# REV5.net
KiCad netlist of a schematic drawn in EasyEDA Pro
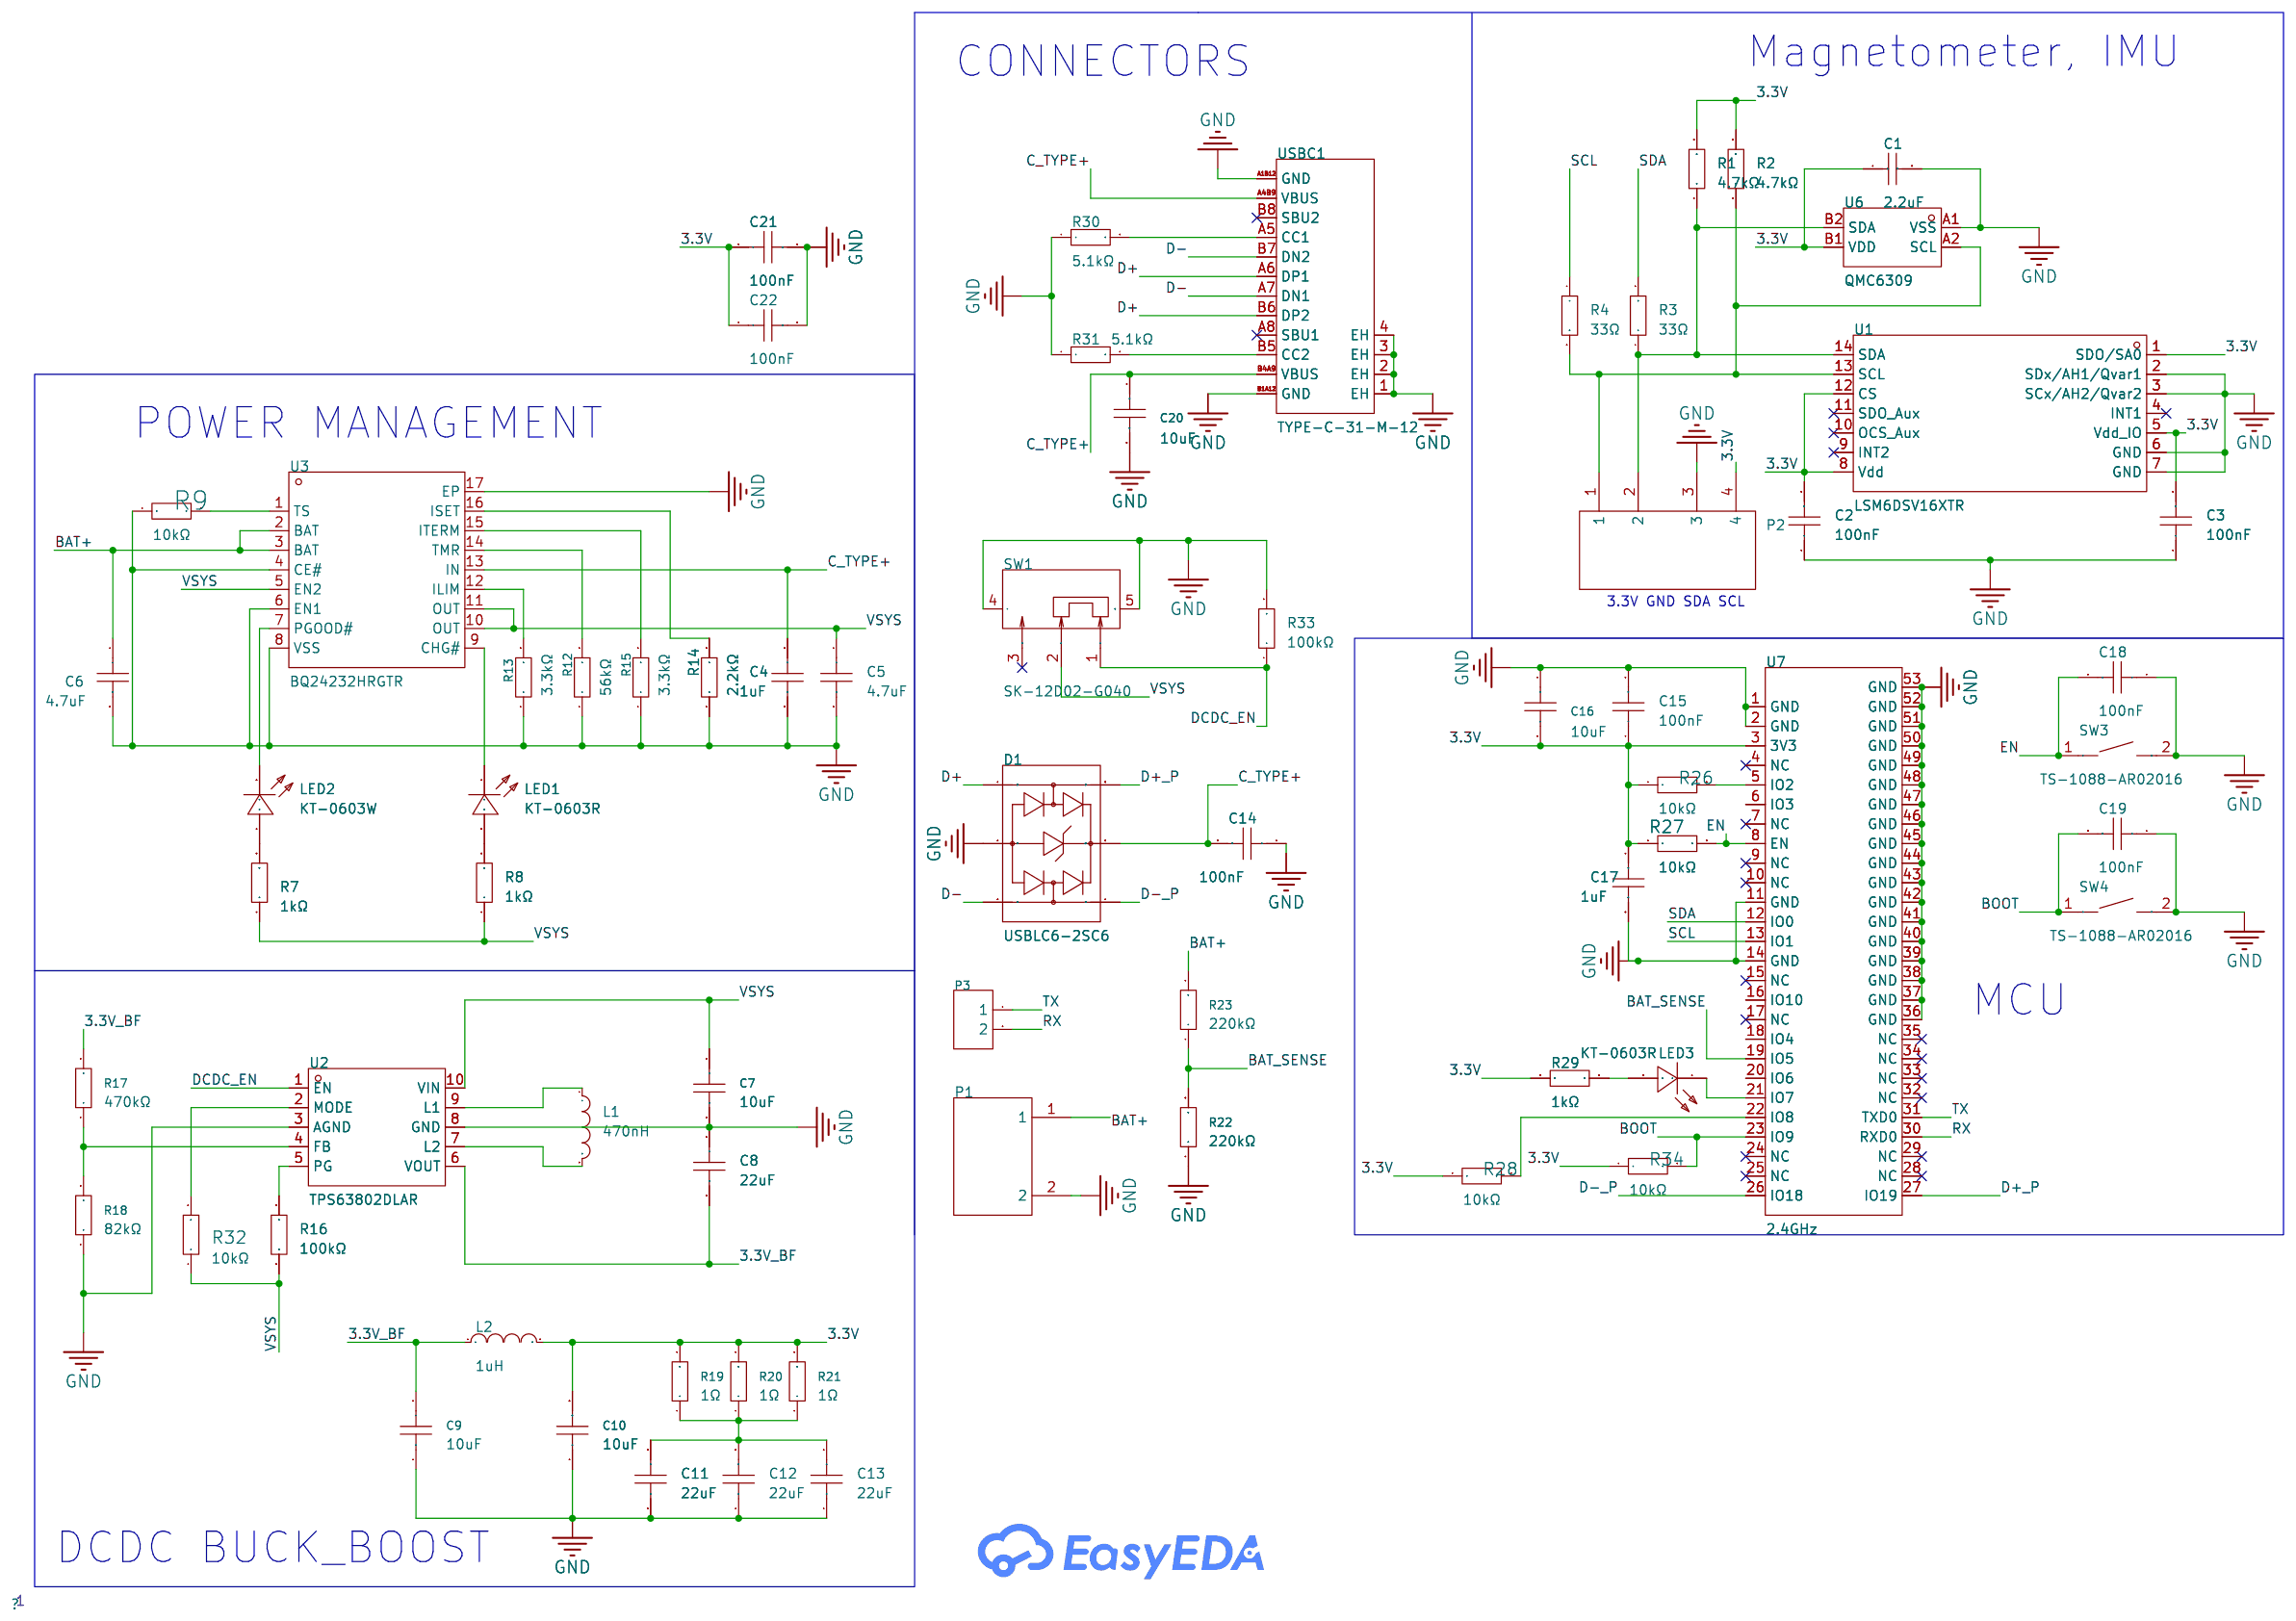
[diagram p0: schematic sheet]

(export (version "E")
  (design (tool "Eeschema 10.0.6"))
  (components
    (comp (ref "C1")
      (value "2.2uF")
      (footprint "easyedapro:C0603")
      (description "Capacitance:2.2uF Tolerance:±10% Tolerance:±10% Voltage Rating:16V Temperature Coefficient:X5R")
      (fields
        (field (name "Manufacturer Part") "CL10A225KO8NNNC")
        (field (name "Manufacturer") "SAMSUNG(三星)")
      )
      (libsource (lib "easyedapro") (part "CL10A225KO8NNNC"))
    )
    (comp (ref "C2")
      (value "100nF")
      (footprint "easyedapro:C0603")
      (description "Capacitance:100nF Tolerance:±10% Tolerance:±10% Voltage Rating:50V Temperature Coefficient:X7R")
      (fields
        (field (name "Manufacturer Part") "CC0603KRX7R9BB104")
        (field (name "Manufacturer") "YAGEO(国巨)")
      )
      (libsource (lib "easyedapro") (part "CC0603KRX7R9BB104"))
    )
    (comp (ref "C3")
      (value "100nF")
      (footprint "easyedapro:C0603")
      (description "Capacitance:100nF Tolerance:±10% Tolerance:±10% Voltage Rating:50V Temperature Coefficient:X7R")
      (fields
        (field (name "Manufacturer Part") "CC0603KRX7R9BB104")
        (field (name "Manufacturer") "YAGEO(国巨)")
      )
      (libsource (lib "easyedapro") (part "CC0603KRX7R9BB104"))
    )
    (comp (ref "C4")
      (value "1uF")
      (footprint "easyedapro:C0603")
      (description "Capacitance:1uF Tolerance:±10% Tolerance:±10% Voltage Rating:50V Temperature Coefficient:X5R")
      (fields
        (field (name "Manufacturer Part") "CL10A105KB8NNNC")
        (field (name "Manufacturer") "SAMSUNG(三星)")
      )
      (libsource (lib "easyedapro") (part "CL10A105KB8NNNC"))
    )
    (comp (ref "C5")
      (value "4.7uF")
      (footprint "easyedapro:C0603")
      (description "Capacitance:4.7uF Tolerance:±10% Tolerance:±10% Voltage Rating:16V Temperature Coefficient:X5R")
      (fields
        (field (name "Manufacturer Part") "CL10A475KO8NNNC")
        (field (name "Manufacturer") "SAMSUNG(三星)")
      )
      (libsource (lib "easyedapro") (part "CL10A475KO8NNNC"))
    )
    (comp (ref "C6")
      (value "4.7uF")
      (footprint "easyedapro:C0603")
      (description "Capacitance:4.7uF Tolerance:±10% Tolerance:±10% Voltage Rating:16V Temperature Coefficient:X5R")
      (fields
        (field (name "Manufacturer Part") "CL10A475KO8NNNC")
        (field (name "Manufacturer") "SAMSUNG(三星)")
      )
      (libsource (lib "easyedapro") (part "CL10A475KO8NNNC"))
    )
    (comp (ref "C7")
      (value "10uF")
      (footprint "easyedapro:C0603")
      (description "Capacitance:10uF Tolerance:±20% Tolerance:±20% Voltage Rating:25V Temperature Coefficient:X5R")
      (fields
        (field (name "Manufacturer Part") "CL10A106MA8NRNC")
        (field (name "Manufacturer") "SAMSUNG(三星)")
      )
      (libsource (lib "easyedapro") (part "CL10A106MA8NRNC"))
    )
    (comp (ref "C8")
      (value "22uF")
      (footprint "easyedapro:C0805")
      (description "Capacitance:22uF Tolerance:±20% Tolerance:±20% Voltage Rating:25V Temperature Coefficient:X5R")
      (fields
        (field (name "Manufacturer Part") "CL21A226MAQNNNE")
        (field (name "Manufacturer") "SAMSUNG(三星)")
      )
      (libsource (lib "easyedapro") (part "CL21A226MAQNNNE"))
    )
    (comp (ref "C9")
      (value "10uF")
      (footprint "easyedapro:C0603")
      (description "Capacitance:10uF Tolerance:±20% Tolerance:±20% Voltage Rating:25V Temperature Coefficient:X5R")
      (fields
        (field (name "Manufacturer Part") "CL10A106MA8NRNC")
        (field (name "Manufacturer") "SAMSUNG(三星)")
      )
      (libsource (lib "easyedapro") (part "CL10A106MA8NRNC"))
    )
    (comp (ref "C10")
      (value "10uF")
      (footprint "easyedapro:C0603")
      (description "Capacitance:10uF Tolerance:±20% Tolerance:±20% Voltage Rating:25V Temperature Coefficient:X5R")
      (fields
        (field (name "Manufacturer Part") "CL10A106MA8NRNC")
        (field (name "Manufacturer") "SAMSUNG(三星)")
      )
      (libsource (lib "easyedapro") (part "CL10A106MA8NRNC"))
    )
    (comp (ref "C11")
      (value "22uF")
      (footprint "easyedapro:C0805")
      (description "Capacitance:22uF Tolerance:±20% Tolerance:±20% Voltage Rating:25V Temperature Coefficient:X5R")
      (fields
        (field (name "Manufacturer Part") "CL21A226MAQNNNE")
        (field (name "Manufacturer") "SAMSUNG(三星)")
      )
      (libsource (lib "easyedapro") (part "CL21A226MAQNNNE"))
    )
    (comp (ref "C12")
      (value "22uF")
      (footprint "easyedapro:C0805")
      (description "Capacitance:22uF Tolerance:±20% Tolerance:±20% Voltage Rating:25V Temperature Coefficient:X5R")
      (fields
        (field (name "Manufacturer Part") "CL21A226MAQNNNE")
        (field (name "Manufacturer") "SAMSUNG(三星)")
      )
      (libsource (lib "easyedapro") (part "CL21A226MAQNNNE"))
    )
    (comp (ref "C13")
      (value "22uF")
      (footprint "easyedapro:C0805")
      (description "Capacitance:22uF Tolerance:±20% Tolerance:±20% Voltage Rating:25V Temperature Coefficient:X5R")
      (fields
        (field (name "Manufacturer Part") "CL21A226MAQNNNE")
        (field (name "Manufacturer") "SAMSUNG(三星)")
      )
      (libsource (lib "easyedapro") (part "CL21A226MAQNNNE"))
    )
    (comp (ref "C14")
      (value "100nF")
      (footprint "easyedapro:C0603")
      (description "Capacitance:100nF Tolerance:±10% Tolerance:±10% Voltage Rating:50V Temperature Coefficient:X7R")
      (fields
        (field (name "Manufacturer Part") "CC0603KRX7R9BB104")
        (field (name "Manufacturer") "YAGEO(国巨)")
      )
      (libsource (lib "easyedapro") (part "CC0603KRX7R9BB104"))
    )
    (comp (ref "C15")
      (value "100nF")
      (footprint "easyedapro:C0603")
      (description "Capacitance:100nF Tolerance:±10% Tolerance:±10% Voltage Rating:50V Temperature Coefficient:X7R")
      (fields
        (field (name "Manufacturer Part") "CC0603KRX7R9BB104")
        (field (name "Manufacturer") "YAGEO(国巨)")
      )
      (libsource (lib "easyedapro") (part "CC0603KRX7R9BB104"))
    )
    (comp (ref "C16")
      (value "10uF")
      (footprint "easyedapro:C0603")
      (description "Capacitance:10uF Tolerance:±20% Tolerance:±20% Voltage Rating:25V Temperature Coefficient:X5R")
      (fields
        (field (name "Manufacturer Part") "CL10A106MA8NRNC")
        (field (name "Manufacturer") "SAMSUNG(三星)")
      )
      (libsource (lib "easyedapro") (part "CL10A106MA8NRNC"))
    )
    (comp (ref "C17")
      (value "1uF")
      (footprint "easyedapro:C0603")
      (description "Capacitance:1uF Tolerance:±10% Tolerance:±10% Voltage Rating:50V Temperature Coefficient:X5R")
      (fields
        (field (name "Manufacturer Part") "CL10A105KB8NNNC")
        (field (name "Manufacturer") "SAMSUNG(三星)")
      )
      (libsource (lib "easyedapro") (part "CL10A105KB8NNNC"))
    )
    (comp (ref "C18")
      (value "100nF")
      (footprint "easyedapro:C0603")
      (description "Capacitance:100nF Tolerance:±10% Tolerance:±10% Voltage Rating:50V Temperature Coefficient:X7R")
      (fields
        (field (name "Manufacturer Part") "CC0603KRX7R9BB104")
        (field (name "Manufacturer") "YAGEO(国巨)")
      )
      (libsource (lib "easyedapro") (part "CC0603KRX7R9BB104"))
    )
    (comp (ref "C19")
      (value "100nF")
      (footprint "easyedapro:C0603")
      (description "Capacitance:100nF Tolerance:±10% Tolerance:±10% Voltage Rating:50V Temperature Coefficient:X7R")
      (fields
        (field (name "Manufacturer Part") "CC0603KRX7R9BB104")
        (field (name "Manufacturer") "YAGEO(国巨)")
      )
      (libsource (lib "easyedapro") (part "CC0603KRX7R9BB104"))
    )
    (comp (ref "C20")
      (value "10uF")
      (footprint "easyedapro:C0603")
      (description "Capacitance:10uF Tolerance:±20% Tolerance:±20% Voltage Rating:25V Temperature Coefficient:X5R")
      (fields
        (field (name "Manufacturer Part") "CL10A106MA8NRNC")
        (field (name "Manufacturer") "SAMSUNG(三星)")
      )
      (libsource (lib "easyedapro") (part "CL10A106MA8NRNC"))
    )
    (comp (ref "C21")
      (value "100nF")
      (description "Capacitance:100nF Tolerance:±10% Tolerance:±10% Voltage Rating:16V Temperature Coefficient:X7R")
      (fields
        (field (name "Manufacturer Part") "CL05B104KO5NNNC")
        (field (name "Manufacturer") "SAMSUNG(三星)")
      )
      (libsource (lib "easyedapro") (part "CL05B104KO5NNNC"))
    )
    (comp (ref "C22")
      (value "100nF")
      (description "Capacitance:100nF Tolerance:±10% Tolerance:±10% Voltage Rating:16V Temperature Coefficient:X7R")
      (fields
        (field (name "Manufacturer Part") "CL05B104KO5NNNC")
        (field (name "Manufacturer") "SAMSUNG(三星)")
      )
      (libsource (lib "easyedapro") (part "CL05B104KO5NNNC"))
    )
    (comp (ref "D1")
      (value "USBLC6-2SC6")
      (footprint "easyedapro:SOT-23-6_L2.9-W1.6-P0.95-LS2.8-BL")
      (fields (field (name "Manufacturer") "GOODWORK(固得沃克)"))
      (libsource (lib "easyedapro") (part "USBLC6-2SC6_C21713975"))
    )
    (comp (ref "L1")
      (value "470nH")
      (footprint "easyedapro:IND-SMD_L2.0-W1.6-1")
      (fields
        (field (name "Manufacturer Part") "DFE201612E-R47M=P2")
        (field (name "Manufacturer") "muRata(村田)")
      )
      (libsource (lib "easyedapro") (part "DFE201612E-R47M=P2"))
    )
    (comp (ref "L2")
      (value "1uH")
      (footprint "easyedapro:IND-SMD_L3.2-W2.5-1")
      (fields (field (name "Manufacturer Part") "TMS322512ALM-1R0MTAA") (field (name "Manufacturer") "TDK"))
      (libsource (lib "easyedapro") (part "TMS322512ALM-1R0MTAA"))
    )
    (comp (ref "LED1")
      (value "KT-0603R")
      (fields (field (name "Manufacturer") "KENTO"))
      (libsource (lib "easyedapro") (part "KT-0603R"))
    )
    (comp (ref "LED2")
      (value "KT-0603W")
      (footprint "easyedapro:LED0603-R-RD_WHITE")
      (fields (field (name "Manufacturer") "KENTO"))
      (libsource (lib "easyedapro") (part "0603White light_C2290"))
    )
    (comp (ref "LED3")
      (value "KT-0603R")
      (fields (field (name "Manufacturer") "KENTO"))
      (libsource (lib "easyedapro") (part "KT-0603R"))
    )
    (comp (ref "P1") (value "~") (libsource (lib "easyedapro") (part "SMW-250-02P")))
    (comp (ref "P2") (value "~") (libsource (lib "easyedapro") (part "SMW-250-04P")))
    (comp (ref "P3")
      (value "~")
      (footprint "easyedapro:HDR-TH_2P-P2.54-V-F")
      (libsource (lib "easyedapro") (part "Header-Female-2.54_1x2"))
    )
    (comp (ref "R1")
      (value "4.7kΩ")
      (footprint "easyedapro:R0603")
      (fields
        (field (name "Manufacturer Part") "0603WAF4701T5E")
        (field (name "Manufacturer") "UNI-ROYAL(厚声)")
      )
      (libsource (lib "easyedapro") (part "0603WAF4701T5E"))
    )
    (comp (ref "R2")
      (value "4.7kΩ")
      (footprint "easyedapro:R0603")
      (fields
        (field (name "Manufacturer Part") "0603WAF4701T5E")
        (field (name "Manufacturer") "UNI-ROYAL(厚声)")
      )
      (libsource (lib "easyedapro") (part "0603WAF4701T5E"))
    )
    (comp (ref "R3")
      (value "33Ω")
      (footprint "easyedapro:R0603")
      (fields
        (field (name "Manufacturer Part") "0603WAF330JT5E")
        (field (name "Manufacturer") "UNI-ROYAL(厚声)")
      )
      (libsource (lib "easyedapro") (part "0603WAF330JT5E"))
    )
    (comp (ref "R4")
      (value "33Ω")
      (footprint "easyedapro:R0603")
      (fields
        (field (name "Manufacturer Part") "0603WAF330JT5E")
        (field (name "Manufacturer") "UNI-ROYAL(厚声)")
      )
      (libsource (lib "easyedapro") (part "0603WAF330JT5E"))
    )
    (comp (ref "R7")
      (value "1kΩ")
      (footprint "easyedapro:R0603")
      (fields
        (field (name "Manufacturer Part") "0603WAF1001T5E")
        (field (name "Manufacturer") "UNI-ROYAL(厚声)")
      )
      (libsource (lib "easyedapro") (part "0603WAF1001T5E"))
    )
    (comp (ref "R8")
      (value "1kΩ")
      (footprint "easyedapro:R0603")
      (fields
        (field (name "Manufacturer Part") "0603WAF1001T5E")
        (field (name "Manufacturer") "UNI-ROYAL(厚声)")
      )
      (libsource (lib "easyedapro") (part "0603WAF1001T5E"))
    )
    (comp (ref "R9")
      (value "10kΩ")
      (footprint "easyedapro:R0603")
      (fields
        (field (name "Manufacturer Part") "0603WAF1002T5E")
        (field (name "Manufacturer") "UNI-ROYAL(厚声)")
      )
      (libsource (lib "easyedapro") (part "0603WAF1002T5E"))
    )
    (comp (ref "R12")
      (value "56kΩ")
      (footprint "easyedapro:R0603")
      (fields
        (field (name "Manufacturer Part") "0603WAF5602T5E")
        (field (name "Manufacturer") "UNI-ROYAL(厚声)")
      )
      (libsource (lib "easyedapro") (part "0603WAF5602T5E"))
    )
    (comp (ref "R13")
      (value "3.3kΩ")
      (footprint "easyedapro:R0603")
      (fields
        (field (name "Manufacturer Part") "0603WAF3301T5E")
        (field (name "Manufacturer") "UNI-ROYAL(厚声)")
      )
      (libsource (lib "easyedapro") (part "0603WAF3301T5E"))
    )
    (comp (ref "R14")
      (value "2.2kΩ")
      (footprint "easyedapro:R0603")
      (fields
        (field (name "Manufacturer Part") "0603WAF2201T5E")
        (field (name "Manufacturer") "UNI-ROYAL(厚声)")
      )
      (libsource (lib "easyedapro") (part "0603WAF2201T5E"))
    )
    (comp (ref "R15")
      (value "3.3kΩ")
      (footprint "easyedapro:R0603")
      (fields
        (field (name "Manufacturer Part") "0603WAF3301T5E")
        (field (name "Manufacturer") "UNI-ROYAL(厚声)")
      )
      (libsource (lib "easyedapro") (part "0603WAF3301T5E"))
    )
    (comp (ref "R16")
      (value "100kΩ")
      (footprint "easyedapro:R0603")
      (fields
        (field (name "Manufacturer Part") "0603WAF1003T5E")
        (field (name "Manufacturer") "UNI-ROYAL(厚声)")
      )
      (libsource (lib "easyedapro") (part "0603WAF1003T5E"))
    )
    (comp (ref "R17")
      (value "470kΩ")
      (footprint "easyedapro:R0603")
      (fields
        (field (name "Manufacturer Part") "0603WAF4703T5E")
        (field (name "Manufacturer") "UNI-ROYAL(厚声)")
      )
      (libsource (lib "easyedapro") (part "0603WAF4703T5E"))
    )
    (comp (ref "R18")
      (value "82kΩ")
      (footprint "easyedapro:R0603")
      (fields
        (field (name "Manufacturer Part") "0603WAF8202T5E")
        (field (name "Manufacturer") "UNI-ROYAL(厚声)")
      )
      (libsource (lib "easyedapro") (part "0603WAF8202T5E"))
    )
    (comp (ref "R19")
      (value "1Ω")
      (footprint "easyedapro:R0603")
      (fields
        (field (name "Manufacturer Part") "0603WAF100KT5E")
        (field (name "Manufacturer") "UNI-ROYAL(厚声)")
      )
      (libsource (lib "easyedapro") (part "0603WAF100KT5E"))
    )
    (comp (ref "R20")
      (value "1Ω")
      (footprint "easyedapro:R0603")
      (fields
        (field (name "Manufacturer Part") "0603WAF100KT5E")
        (field (name "Manufacturer") "UNI-ROYAL(厚声)")
      )
      (libsource (lib "easyedapro") (part "0603WAF100KT5E"))
    )
    (comp (ref "R21")
      (value "1Ω")
      (footprint "easyedapro:R0603")
      (fields
        (field (name "Manufacturer Part") "0603WAF100KT5E")
        (field (name "Manufacturer") "UNI-ROYAL(厚声)")
      )
      (libsource (lib "easyedapro") (part "0603WAF100KT5E"))
    )
    (comp (ref "R22")
      (value "220kΩ")
      (footprint "easyedapro:R0603")
      (fields
        (field (name "Manufacturer Part") "0603WAF2203T5E")
        (field (name "Manufacturer") "UNI-ROYAL(厚声)")
      )
      (libsource (lib "easyedapro") (part "0603WAF2203T5E"))
    )
    (comp (ref "R23")
      (value "220kΩ")
      (footprint "easyedapro:R0603")
      (fields
        (field (name "Manufacturer Part") "0603WAF2203T5E")
        (field (name "Manufacturer") "UNI-ROYAL(厚声)")
      )
      (libsource (lib "easyedapro") (part "0603WAF2203T5E"))
    )
    (comp (ref "R26")
      (value "10kΩ")
      (footprint "easyedapro:R0603")
      (fields
        (field (name "Manufacturer Part") "0603WAF1002T5E")
        (field (name "Manufacturer") "UNI-ROYAL(厚声)")
      )
      (libsource (lib "easyedapro") (part "0603WAF1002T5E"))
    )
    (comp (ref "R27")
      (value "10kΩ")
      (footprint "easyedapro:R0603")
      (fields
        (field (name "Manufacturer Part") "0603WAF1002T5E")
        (field (name "Manufacturer") "UNI-ROYAL(厚声)")
      )
      (libsource (lib "easyedapro") (part "0603WAF1002T5E"))
    )
    (comp (ref "R28")
      (value "10kΩ")
      (footprint "easyedapro:R0603")
      (fields
        (field (name "Manufacturer Part") "0603WAF1002T5E")
        (field (name "Manufacturer") "UNI-ROYAL(厚声)")
      )
      (libsource (lib "easyedapro") (part "0603WAF1002T5E"))
    )
    (comp (ref "R29")
      (value "1kΩ")
      (footprint "easyedapro:R0603")
      (fields
        (field (name "Manufacturer Part") "0603WAF1001T5E")
        (field (name "Manufacturer") "UNI-ROYAL(厚声)")
      )
      (libsource (lib "easyedapro") (part "0603WAF1001T5E"))
    )
    (comp (ref "R30")
      (value "5.1kΩ")
      (footprint "easyedapro:R0603")
      (fields
        (field (name "Manufacturer Part") "0603WAF5101T5E")
        (field (name "Manufacturer") "UNI-ROYAL(厚声)")
      )
      (libsource (lib "easyedapro") (part "0603WAF5101T5E"))
    )
    (comp (ref "R31")
      (value "5.1kΩ")
      (footprint "easyedapro:R0603")
      (fields
        (field (name "Manufacturer Part") "0603WAF5101T5E")
        (field (name "Manufacturer") "UNI-ROYAL(厚声)")
      )
      (libsource (lib "easyedapro") (part "0603WAF5101T5E"))
    )
    (comp (ref "R32")
      (value "10kΩ")
      (footprint "easyedapro:R0603")
      (fields
        (field (name "Manufacturer Part") "0603WAF1002T5E")
        (field (name "Manufacturer") "UNI-ROYAL(厚声)")
      )
      (libsource (lib "easyedapro") (part "0603WAF1002T5E"))
    )
    (comp (ref "R33")
      (value "100kΩ")
      (footprint "easyedapro:R0603")
      (fields
        (field (name "Manufacturer Part") "0603WAF1003T5E")
        (field (name "Manufacturer") "UNI-ROYAL(厚声)")
      )
      (libsource (lib "easyedapro") (part "0603WAF1003T5E"))
    )
    (comp (ref "R34")
      (value "10kΩ")
      (footprint "easyedapro:R0603")
      (fields
        (field (name "Manufacturer Part") "0603WAF1002T5E")
        (field (name "Manufacturer") "UNI-ROYAL(厚声)")
      )
      (libsource (lib "easyedapro") (part "0603WAF1002T5E"))
    )
    (comp (ref "SW1")
      (value "SK-12D02-G040")
      (footprint "easyedapro:SW-TH_SK-12D02-G040")
      (fields (field (name "Manufacturer") "G-Switch(品赞)"))
      (libsource (lib "easyedapro") (part "SK-12D02-G040"))
    )
    (comp (ref "SW3")
      (value "TS-1088-AR02016")
      (footprint "easyedapro:SW-SMD_L3.9-W3.0-P4.45")
      (fields (field (name "Manufacturer") "XUNPU(讯普)"))
      (libsource (lib "easyedapro") (part "TS-1088-AR02016"))
    )
    (comp (ref "SW4")
      (value "TS-1088-AR02016")
      (footprint "easyedapro:SW-SMD_L3.9-W3.0-P4.45")
      (fields (field (name "Manufacturer") "XUNPU(讯普)"))
      (libsource (lib "easyedapro") (part "TS-1088-AR02016"))
    )
    (comp (ref "U1")
      (value "LSM6DSV16XTR")
      (footprint "easyedapro:LGA-14_L3.0-W2.5-P0.50-BR")
      (fields (field (name "Manufacturer") "ST(意法半导体)"))
      (libsource (lib "easyedapro") (part "LSM6DSV16XTR"))
    )
    (comp (ref "U2")
      (value "TPS63802DLAR")
      (footprint "easyedapro:VSON-10_L3.0-W2.0-P0.50-TL")
      (fields (field (name "Manufacturer") "TI(德州仪器)"))
      (libsource (lib "easyedapro") (part "TPS63802DLAR"))
    )
    (comp (ref "U3")
      (value "BQ24232HRGTR")
      (footprint "easyedapro:VQFN-16_L3.0-W3.0-P0.50-TL-EP1.7")
      (fields (field (name "Manufacturer") "TI(德州仪器)"))
      (libsource (lib "easyedapro") (part "BQ24232HRGTR"))
    )
    (comp (ref "U6")
      (value "QMC6309")
      (footprint "easyedapro:X1-WLB0808-4_L0.8-W0.8-P0.40-TL")
      (fields (field (name "Manufacturer") "QST(上海矽睿)"))
      (libsource (lib "easyedapro") (part "QMC6309"))
    )
    (comp (ref "U7")
      (value "2.4GHz")
      (footprint "easyedapro:WIFIM-SMD_ESP32-C3-MINI-1")
      (fields
        (field (name "Manufacturer Part") "ESP32-C3-MINI-1-H4X")
        (field (name "Manufacturer") "ESPRESSIF(乐鑫)")
      )
      (libsource (lib "easyedapro") (part "ESP32-C3-MINI-1-H4X"))
    )
    (comp (ref "USBC1")
      (value "TYPE-C-31-M-12")
      (footprint "easyedapro:USB-C_SMD-TYPE-C-31-M-12_1")
      (fields (field (name "Manufacturer") "韩国韩荣"))
      (libsource (lib "easyedapro") (part "TYPE-C-31-M-12"))
    )
  )
  (nets
    (net (code "1") (name "/3.3V") (class "Default")
      (node (ref "C1") (pin "1") (pinfunction "1_1") (pintype "input"))
      (node (ref "C10") (pin "2") (pinfunction "2_2") (pintype "input"))
      (node (ref "C15") (pin "1") (pinfunction "1_1") (pintype "unspecified"))
      (node (ref "C16") (pin "2") (pinfunction "2_2") (pintype "input"))
      (node (ref "C17") (pin "1") (pinfunction "1_1") (pintype "unspecified"))
      (node (ref "C2") (pin "2") (pinfunction "2_2") (pintype "unspecified"))
      (node (ref "C21") (pin "1") (pinfunction "1_1") (pintype "unspecified"))
      (node (ref "C22") (pin "1") (pinfunction "1_1") (pintype "unspecified"))
      (node (ref "C3") (pin "2") (pinfunction "2_2") (pintype "unspecified"))
      (node (ref "L2") (pin "2") (pinfunction "2_2") (pintype "unspecified"))
      (node (ref "P2") (pin "4") (pinfunction "4_4") (pintype "input"))
      (node (ref "R1") (pin "2") (pinfunction "2_2") (pintype "input"))
      (node (ref "R19") (pin "2") (pinfunction "2_2") (pintype "input"))
      (node (ref "R2") (pin "2") (pinfunction "2_2") (pintype "input"))
      (node (ref "R20") (pin "2") (pinfunction "2_2") (pintype "input"))
      (node (ref "R21") (pin "2") (pinfunction "2_2") (pintype "input"))
      (node (ref "R26") (pin "1") (pinfunction "1_1") (pintype "input"))
      (node (ref "R27") (pin "1") (pinfunction "1_1") (pintype "input"))
      (node (ref "R28") (pin "1") (pinfunction "1_1") (pintype "input"))
      (node (ref "R29") (pin "2") (pinfunction "2_2") (pintype "input"))
      (node (ref "R34") (pin "1") (pinfunction "1_1") (pintype "input"))
      (node (ref "U1") (pin "1") (pinfunction "SDO/SA0_1") (pintype "unspecified"))
      (node (ref "U1") (pin "12") (pinfunction "CS_12") (pintype "unspecified"))
      (node (ref "U1") (pin "5") (pinfunction "Vdd_IO_5") (pintype "unspecified"))
      (node (ref "U1") (pin "8") (pinfunction "Vdd_8") (pintype "unspecified"))
      (node (ref "U6") (pin "B1") (pinfunction "VDD_B1") (pintype "unspecified"))
      (node (ref "U7") (pin "3") (pinfunction "3V3_3") (pintype "unspecified"))
    )
    (net (code "2") (name "/3.3V_BF") (class "Default")
      (node (ref "C8") (pin "2") (pinfunction "2_2") (pintype "unspecified"))
      (node (ref "C9") (pin "2") (pinfunction "2_2") (pintype "input"))
      (node (ref "L2") (pin "1") (pinfunction "1_1") (pintype "unspecified"))
      (node (ref "R17") (pin "2") (pinfunction "2_2") (pintype "input"))
      (node (ref "U2") (pin "6") (pinfunction "VOUT_6") (pintype "unspecified"))
    )
    (net (code "3") (name "/BAT+") (class "Default")
      (node (ref "C6") (pin "1") (pinfunction "1_1") (pintype "unspecified"))
      (node (ref "P1") (pin "1") (pinfunction "1_1") (pintype "input"))
      (node (ref "R23") (pin "2") (pinfunction "2_2") (pintype "input"))
      (node (ref "U3") (pin "2") (pinfunction "BAT_2") (pintype "unspecified"))
      (node (ref "U3") (pin "3") (pinfunction "BAT_3") (pintype "unspecified"))
    )
    (net (code "4") (name "/BAT_SENSE") (class "Default")
      (node (ref "R22") (pin "2") (pinfunction "2_2") (pintype "input"))
      (node (ref "R23") (pin "1") (pinfunction "1_1") (pintype "input"))
      (node (ref "U7") (pin "19") (pinfunction "IO5_19") (pintype "unspecified"))
    )
    (net (code "5") (name "/BOOT") (class "Default")
      (node (ref "C19") (pin "2") (pinfunction "2_2") (pintype "unspecified"))
      (node (ref "R34") (pin "2") (pinfunction "2_2") (pintype "input"))
      (node (ref "SW4") (pin "1") (pinfunction "1_1") (pintype "unspecified"))
      (node (ref "U7") (pin "23") (pinfunction "IO9_23") (pintype "unspecified"))
    )
    (net (code "6") (name "/C_TYPE+") (class "Default")
      (node (ref "C14") (pin "2") (pinfunction "2_2") (pintype "unspecified"))
      (node (ref "C20") (pin "1") (pinfunction "1_1") (pintype "input"))
      (node (ref "C4") (pin "1") (pinfunction "1_1") (pintype "unspecified"))
      (node (ref "D1") (pin "5") (pinfunction "VBUS_5") (pintype "unspecified"))
      (node (ref "U3") (pin "13") (pinfunction "IN_13") (pintype "unspecified"))
      (node (ref "USBC1") (pin "A4B9") (pinfunction "VBUS_A4B9") (pintype "unspecified"))
      (node (ref "USBC1") (pin "B4A9") (pinfunction "VBUS_B4A9") (pintype "unspecified"))
    )
    (net (code "7") (name "/D+") (class "Default")
      (node (ref "D1") (pin "1") (pinfunction "I/O1_1") (pintype "unspecified"))
      (node (ref "USBC1") (pin "A6") (pinfunction "DP1_A6") (pintype "unspecified"))
      (node (ref "USBC1") (pin "B6") (pinfunction "DP2_B6") (pintype "unspecified"))
    )
    (net (code "8") (name "/D+_P") (class "Default")
      (node (ref "D1") (pin "6") (pinfunction "I/O1_6") (pintype "unspecified"))
      (node (ref "U7") (pin "27") (pinfunction "IO19_27") (pintype "unspecified"))
    )
    (net (code "9") (name "/D-") (class "Default")
      (node (ref "D1") (pin "3") (pinfunction "I/O2_3") (pintype "unspecified"))
      (node (ref "USBC1") (pin "A7") (pinfunction "DN1_A7") (pintype "unspecified"))
      (node (ref "USBC1") (pin "B7") (pinfunction "DN2_B7") (pintype "unspecified"))
    )
    (net (code "10") (name "/D-_P") (class "Default")
      (node (ref "D1") (pin "4") (pinfunction "I/O2_4") (pintype "unspecified"))
      (node (ref "U7") (pin "26") (pinfunction "IO18_26") (pintype "unspecified"))
    )
    (net (code "11") (name "/DCDC_EN") (class "Default")
      (node (ref "R33") (pin "1") (pinfunction "1_1") (pintype "input"))
      (node (ref "SW1") (pin "1") (pinfunction "1_1") (pintype "unspecified"))
      (node (ref "U2") (pin "1") (pinfunction "EN_1") (pintype "unspecified"))
    )
    (net (code "12") (name "/EN") (class "Default")
      (node (ref "C18") (pin "2") (pinfunction "2_2") (pintype "unspecified"))
      (node (ref "R27") (pin "2") (pinfunction "2_2") (pintype "input"))
      (node (ref "SW3") (pin "1") (pinfunction "1_1") (pintype "unspecified"))
      (node (ref "U7") (pin "8") (pinfunction "EN_8") (pintype "unspecified"))
    )
    (net (code "13") (name "/RX") (class "Default")
      (node (ref "P3") (pin "2") (pinfunction "2_2") (pintype "input"))
      (node (ref "U7") (pin "30") (pinfunction "RXD0_30") (pintype "unspecified"))
    )
    (net (code "14") (name "/SCL") (class "Default")
      (node (ref "R4") (pin "1") (pinfunction "1_1") (pintype "input"))
      (node (ref "U7") (pin "13") (pinfunction "IO1_13") (pintype "unspecified"))
    )
    (net (code "15") (name "/SDA") (class "Default")
      (node (ref "R3") (pin "2") (pinfunction "2_2") (pintype "input"))
      (node (ref "U7") (pin "12") (pinfunction "IO0_12") (pintype "unspecified"))
    )
    (net (code "16") (name "/TX") (class "Default")
      (node (ref "P3") (pin "1") (pinfunction "1_1") (pintype "input"))
      (node (ref "U7") (pin "31") (pinfunction "TXD0_31") (pintype "unspecified"))
    )
    (net (code "17") (name "/VSYS") (class "Default")
      (node (ref "C5") (pin "1") (pinfunction "1_1") (pintype "unspecified"))
      (node (ref "C7") (pin "1") (pinfunction "1_1") (pintype "input"))
      (node (ref "R16") (pin "1") (pinfunction "1_1") (pintype "input"))
      (node (ref "R32") (pin "1") (pinfunction "1_1") (pintype "input"))
      (node (ref "R7") (pin "1") (pinfunction "1_1") (pintype "input"))
      (node (ref "R8") (pin "1") (pinfunction "1_1") (pintype "input"))
      (node (ref "SW1") (pin "2") (pinfunction "2_2") (pintype "unspecified"))
      (node (ref "U2") (pin "10") (pinfunction "VIN_10") (pintype "unspecified"))
      (node (ref "U3") (pin "10") (pinfunction "OUT_10") (pintype "unspecified"))
      (node (ref "U3") (pin "11") (pinfunction "OUT_11") (pintype "unspecified"))
      (node (ref "U3") (pin "5") (pinfunction "EN2_5") (pintype "unspecified"))
    )
    (net (code "18") (name "GND") (class "Default")
      (node (ref "C1") (pin "2") (pinfunction "2_2") (pintype "input"))
      (node (ref "C10") (pin "1") (pinfunction "1_1") (pintype "input"))
      (node (ref "C11") (pin "1") (pinfunction "1_1") (pintype "unspecified"))
      (node (ref "C12") (pin "1") (pinfunction "1_1") (pintype "unspecified"))
      (node (ref "C13") (pin "1") (pinfunction "1_1") (pintype "unspecified"))
      (node (ref "C14") (pin "1") (pinfunction "1_1") (pintype "unspecified"))
      (node (ref "C15") (pin "2") (pinfunction "2_2") (pintype "unspecified"))
      (node (ref "C16") (pin "1") (pinfunction "1_1") (pintype "input"))
      (node (ref "C17") (pin "2") (pinfunction "2_2") (pintype "unspecified"))
      (node (ref "C18") (pin "1") (pinfunction "1_1") (pintype "unspecified"))
      (node (ref "C19") (pin "1") (pinfunction "1_1") (pintype "unspecified"))
      (node (ref "C2") (pin "1") (pinfunction "1_1") (pintype "unspecified"))
      (node (ref "C20") (pin "2") (pinfunction "2_2") (pintype "input"))
      (node (ref "C21") (pin "2") (pinfunction "2_2") (pintype "unspecified"))
      (node (ref "C22") (pin "2") (pinfunction "2_2") (pintype "unspecified"))
      (node (ref "C3") (pin "1") (pinfunction "1_1") (pintype "unspecified"))
      (node (ref "C4") (pin "2") (pinfunction "2_2") (pintype "unspecified"))
      (node (ref "C5") (pin "2") (pinfunction "2_2") (pintype "unspecified"))
      (node (ref "C6") (pin "2") (pinfunction "2_2") (pintype "unspecified"))
      (node (ref "C7") (pin "2") (pinfunction "2_2") (pintype "input"))
      (node (ref "C8") (pin "1") (pinfunction "1_1") (pintype "unspecified"))
      (node (ref "C9") (pin "1") (pinfunction "1_1") (pintype "input"))
      (node (ref "D1") (pin "2") (pinfunction "GND_2") (pintype "unspecified"))
      (node (ref "P1") (pin "2") (pinfunction "2_2") (pintype "input"))
      (node (ref "P2") (pin "3") (pinfunction "3_3") (pintype "input"))
      (node (ref "R12") (pin "1") (pinfunction "1_1") (pintype "input"))
      (node (ref "R13") (pin "1") (pinfunction "1_1") (pintype "input"))
      (node (ref "R14") (pin "1") (pinfunction "1_1") (pintype "input"))
      (node (ref "R15") (pin "1") (pinfunction "1_1") (pintype "input"))
      (node (ref "R18") (pin "1") (pinfunction "1_1") (pintype "input"))
      (node (ref "R22") (pin "1") (pinfunction "1_1") (pintype "input"))
      (node (ref "R30") (pin "1") (pinfunction "1_1") (pintype "input"))
      (node (ref "R31") (pin "1") (pinfunction "1_1") (pintype "input"))
      (node (ref "R33") (pin "2") (pinfunction "2_2") (pintype "input"))
      (node (ref "R9") (pin "1") (pinfunction "1_1") (pintype "input"))
      (node (ref "SW1") (pin "4") (pinfunction "4_4") (pintype "unspecified"))
      (node (ref "SW1") (pin "5") (pinfunction "5_5") (pintype "unspecified"))
      (node (ref "SW3") (pin "2") (pinfunction "2_2") (pintype "unspecified"))
      (node (ref "SW4") (pin "2") (pinfunction "2_2") (pintype "unspecified"))
      (node (ref "U1") (pin "2") (pinfunction "SDx/AH1/Qvar1_2") (pintype "unspecified"))
      (node (ref "U1") (pin "3") (pinfunction "SCx/AH2/Qvar2_3") (pintype "unspecified"))
      (node (ref "U1") (pin "6") (pinfunction "GND_6") (pintype "unspecified"))
      (node (ref "U1") (pin "7") (pinfunction "GND_7") (pintype "unspecified"))
      (node (ref "U2") (pin "3") (pinfunction "AGND_3") (pintype "unspecified"))
      (node (ref "U2") (pin "8") (pinfunction "GND_8") (pintype "unspecified"))
      (node (ref "U3") (pin "17") (pinfunction "EP_17") (pintype "unspecified"))
      (node (ref "U3") (pin "4") (pinfunction "CE#_4") (pintype "unspecified"))
      (node (ref "U3") (pin "6") (pinfunction "EN1_6") (pintype "unspecified"))
      (node (ref "U3") (pin "8") (pinfunction "VSS_8") (pintype "unspecified"))
      (node (ref "U6") (pin "A1") (pinfunction "VSS_A1") (pintype "unspecified"))
      (node (ref "U7") (pin "1") (pinfunction "GND_1") (pintype "unspecified"))
      (node (ref "U7") (pin "11") (pinfunction "GND_11") (pintype "unspecified"))
      (node (ref "U7") (pin "14") (pinfunction "GND_14") (pintype "unspecified"))
      (node (ref "U7") (pin "2") (pinfunction "GND_2") (pintype "unspecified"))
      (node (ref "U7") (pin "36") (pinfunction "GND_36") (pintype "unspecified"))
      (node (ref "U7") (pin "37") (pinfunction "GND_37") (pintype "unspecified"))
      (node (ref "U7") (pin "38") (pinfunction "GND_38") (pintype "unspecified"))
      (node (ref "U7") (pin "39") (pinfunction "GND_39") (pintype "unspecified"))
      (node (ref "U7") (pin "40") (pinfunction "GND_40") (pintype "unspecified"))
      (node (ref "U7") (pin "41") (pinfunction "GND_41") (pintype "unspecified"))
      (node (ref "U7") (pin "42") (pinfunction "GND_42") (pintype "unspecified"))
      (node (ref "U7") (pin "43") (pinfunction "GND_43") (pintype "unspecified"))
      (node (ref "U7") (pin "44") (pinfunction "GND_44") (pintype "unspecified"))
      (node (ref "U7") (pin "45") (pinfunction "GND_45") (pintype "unspecified"))
      (node (ref "U7") (pin "46") (pinfunction "GND_46") (pintype "unspecified"))
      (node (ref "U7") (pin "47") (pinfunction "GND_47") (pintype "unspecified"))
      (node (ref "U7") (pin "48") (pinfunction "GND_48") (pintype "unspecified"))
      (node (ref "U7") (pin "49") (pinfunction "GND_49") (pintype "unspecified"))
      (node (ref "U7") (pin "50") (pinfunction "GND_50") (pintype "unspecified"))
      (node (ref "U7") (pin "51") (pinfunction "GND_51") (pintype "unspecified"))
      (node (ref "U7") (pin "52") (pinfunction "GND_52") (pintype "unspecified"))
      (node (ref "U7") (pin "53") (pinfunction "GND_53") (pintype "unspecified"))
      (node (ref "USBC1") (pin "1") (pinfunction "EH_1") (pintype "unspecified"))
      (node (ref "USBC1") (pin "2") (pinfunction "EH_2") (pintype "unspecified"))
      (node (ref "USBC1") (pin "3") (pinfunction "EH_3") (pintype "unspecified"))
      (node (ref "USBC1") (pin "4") (pinfunction "EH_4") (pintype "unspecified"))
      (node (ref "USBC1") (pin "A1B12") (pinfunction "GND_A1B12") (pintype "unspecified"))
      (node (ref "USBC1") (pin "B1A12") (pinfunction "GND_B1A12") (pintype "unspecified"))
    )
    (net (code "19") (name "Net-(C11-Pad2)") (class "Default")
      (node (ref "C11") (pin "2") (pinfunction "2_2") (pintype "unspecified"))
      (node (ref "C12") (pin "2") (pinfunction "2_2") (pintype "unspecified"))
      (node (ref "C13") (pin "2") (pinfunction "2_2") (pintype "unspecified"))
      (node (ref "R19") (pin "1") (pinfunction "1_1") (pintype "input"))
      (node (ref "R20") (pin "1") (pinfunction "1_1") (pintype "input"))
      (node (ref "R21") (pin "1") (pinfunction "1_1") (pintype "input"))
    )
    (net (code "20") (name "Net-(LED1-A)") (class "Default")
      (node (ref "LED1") (pin "2") (pinfunction "A_2") (pintype "unspecified"))
      (node (ref "R8") (pin "2") (pinfunction "2_2") (pintype "input"))
    )
    (net (code "21") (name "Net-(LED1-K)") (class "Default")
      (node (ref "LED1") (pin "1") (pinfunction "K_1") (pintype "unspecified"))
      (node (ref "U3") (pin "9") (pinfunction "CHG#_9") (pintype "unspecified"))
    )
    (net (code "22") (name "Net-(LED2-A)") (class "Default")
      (node (ref "LED2") (pin "1") (pinfunction "A_1") (pintype "unspecified"))
      (node (ref "R7") (pin "2") (pinfunction "2_2") (pintype "input"))
    )
    (net (code "23") (name "Net-(LED2-K)") (class "Default")
      (node (ref "LED2") (pin "2") (pinfunction "K_2") (pintype "unspecified"))
      (node (ref "U3") (pin "7") (pinfunction "PGOOD#_7") (pintype "unspecified"))
    )
    (net (code "24") (name "Net-(LED3-A)") (class "Default")
      (node (ref "LED3") (pin "2") (pinfunction "A_2") (pintype "unspecified"))
      (node (ref "R29") (pin "1") (pinfunction "1_1") (pintype "input"))
    )
    (net (code "25") (name "Net-(LED3-K)") (class "Default")
      (node (ref "LED3") (pin "1") (pinfunction "K_1") (pintype "unspecified"))
      (node (ref "U7") (pin "21") (pinfunction "IO7_21") (pintype "unspecified"))
    )
    (net (code "26") (name "Net-(U1-SCL)") (class "Default")
      (node (ref "P2") (pin "1") (pinfunction "1_1") (pintype "input"))
      (node (ref "R2") (pin "1") (pinfunction "1_1") (pintype "input"))
      (node (ref "R4") (pin "2") (pinfunction "2_2") (pintype "input"))
      (node (ref "U1") (pin "13") (pinfunction "SCL_13") (pintype "unspecified"))
      (node (ref "U6") (pin "A2") (pinfunction "SCL_A2") (pintype "unspecified"))
    )
    (net (code "27") (name "Net-(U1-SDA)") (class "Default")
      (node (ref "P2") (pin "2") (pinfunction "2_2") (pintype "input"))
      (node (ref "R1") (pin "1") (pinfunction "1_1") (pintype "input"))
      (node (ref "R3") (pin "1") (pinfunction "1_1") (pintype "input"))
      (node (ref "U1") (pin "14") (pinfunction "SDA_14") (pintype "unspecified"))
      (node (ref "U6") (pin "B2") (pinfunction "SDA_B2") (pintype "unspecified"))
    )
    (net (code "28") (name "Net-(U2-FB)") (class "Default")
      (node (ref "R17") (pin "1") (pinfunction "1_1") (pintype "input"))
      (node (ref "R18") (pin "2") (pinfunction "2_2") (pintype "input"))
      (node (ref "U2") (pin "4") (pinfunction "FB_4") (pintype "unspecified"))
    )
    (net (code "29") (name "Net-(U2-L1)") (class "Default")
      (node (ref "L1") (pin "1") (pinfunction "1_1") (pintype "unspecified"))
      (node (ref "U2") (pin "9") (pinfunction "L1_9") (pintype "unspecified"))
    )
    (net (code "30") (name "Net-(U2-L2)") (class "Default")
      (node (ref "L1") (pin "2") (pinfunction "2_2") (pintype "unspecified"))
      (node (ref "U2") (pin "7") (pinfunction "L2_7") (pintype "unspecified"))
    )
    (net (code "31") (name "Net-(U2-MODE)") (class "Default")
      (node (ref "R32") (pin "2") (pinfunction "2_2") (pintype "input"))
      (node (ref "U2") (pin "2") (pinfunction "MODE_2") (pintype "unspecified"))
    )
    (net (code "32") (name "Net-(U2-PG)") (class "Default")
      (node (ref "R16") (pin "2") (pinfunction "2_2") (pintype "input"))
      (node (ref "U2") (pin "5") (pinfunction "PG_5") (pintype "unspecified"))
    )
    (net (code "33") (name "Net-(U3-ILIM)") (class "Default")
      (node (ref "R13") (pin "2") (pinfunction "2_2") (pintype "input"))
      (node (ref "U3") (pin "12") (pinfunction "ILIM_12") (pintype "unspecified"))
    )
    (net (code "34") (name "Net-(U3-ISET)") (class "Default")
      (node (ref "R14") (pin "2") (pinfunction "2_2") (pintype "input"))
      (node (ref "U3") (pin "16") (pinfunction "ISET_16") (pintype "unspecified"))
    )
    (net (code "35") (name "Net-(U3-ITERM)") (class "Default")
      (node (ref "R15") (pin "2") (pinfunction "2_2") (pintype "input"))
      (node (ref "U3") (pin "15") (pinfunction "ITERM_15") (pintype "unspecified"))
    )
    (net (code "36") (name "Net-(U3-TMR)") (class "Default")
      (node (ref "R12") (pin "2") (pinfunction "2_2") (pintype "input"))
      (node (ref "U3") (pin "14") (pinfunction "TMR_14") (pintype "unspecified"))
    )
    (net (code "37") (name "Net-(U3-TS)") (class "Default")
      (node (ref "R9") (pin "2") (pinfunction "2_2") (pintype "input"))
      (node (ref "U3") (pin "1") (pinfunction "TS_1") (pintype "unspecified"))
    )
    (net (code "38") (name "Net-(U7-IO2)") (class "Default")
      (node (ref "R26") (pin "2") (pinfunction "2_2") (pintype "input"))
      (node (ref "U7") (pin "5") (pinfunction "IO2_5") (pintype "unspecified"))
    )
    (net (code "39") (name "Net-(U7-IO8)") (class "Default")
      (node (ref "R28") (pin "2") (pinfunction "2_2") (pintype "input"))
      (node (ref "U7") (pin "22") (pinfunction "IO8_22") (pintype "unspecified"))
    )
    (net (code "40") (name "Net-(USBC1-CC1)") (class "Default")
      (node (ref "R30") (pin "2") (pinfunction "2_2") (pintype "input"))
      (node (ref "USBC1") (pin "A5") (pinfunction "CC1_A5") (pintype "unspecified"))
    )
    (net (code "41") (name "Net-(USBC1-CC2)") (class "Default")
      (node (ref "R31") (pin "2") (pinfunction "2_2") (pintype "input"))
      (node (ref "USBC1") (pin "B5") (pinfunction "CC2_B5") (pintype "unspecified"))
    )
    (net (code "42") (name "unconnected-(SW1-Pad3)") (class "Default")
      (node (ref "SW1") (pin "3") (pinfunction "3_3") (pintype "unspecified+no_connect"))
    )
    (net (code "43") (name "unconnected-(U1-INT1-Pad4)") (class "Default")
      (node (ref "U1") (pin "4") (pinfunction "INT1_4") (pintype "unspecified+no_connect"))
    )
    (net (code "44") (name "unconnected-(U1-INT2-Pad9)") (class "Default")
      (node (ref "U1") (pin "9") (pinfunction "INT2_9") (pintype "unspecified+no_connect"))
    )
    (net (code "45") (name "unconnected-(U1-OCS_Aux-Pad10)") (class "Default")
      (node (ref "U1") (pin "10") (pinfunction "OCS_Aux_10") (pintype "unspecified+no_connect"))
    )
    (net (code "46") (name "unconnected-(U1-SDO_Aux-Pad11)") (class "Default")
      (node (ref "U1") (pin "11") (pinfunction "SDO_Aux_11") (pintype "unspecified+no_connect"))
    )
    (net (code "47") (name "unconnected-(U7-IO3-Pad6)") (class "Default")
      (node (ref "U7") (pin "6") (pinfunction "IO3_6") (pintype "unspecified"))
    )
    (net (code "48") (name "unconnected-(U7-IO4-Pad18)") (class "Default")
      (node (ref "U7") (pin "18") (pinfunction "IO4_18") (pintype "unspecified"))
    )
    (net (code "49") (name "unconnected-(U7-IO6-Pad20)") (class "Default")
      (node (ref "U7") (pin "20") (pinfunction "IO6_20") (pintype "unspecified"))
    )
    (net (code "50") (name "unconnected-(U7-IO10-Pad16)") (class "Default")
      (node (ref "U7") (pin "16") (pinfunction "IO10_16") (pintype "unspecified"))
    )
    (net (code "51") (name "unconnected-(U7-NC-Pad4)") (class "Default")
      (node (ref "U7") (pin "4") (pinfunction "NC_4") (pintype "unspecified+no_connect"))
    )
    (net (code "52") (name "unconnected-(U7-NC-Pad7)") (class "Default")
      (node (ref "U7") (pin "7") (pinfunction "NC_7") (pintype "unspecified+no_connect"))
    )
    (net (code "53") (name "unconnected-(U7-NC-Pad9)") (class "Default")
      (node (ref "U7") (pin "9") (pinfunction "NC_9") (pintype "unspecified+no_connect"))
    )
    (net (code "54") (name "unconnected-(U7-NC-Pad10)") (class "Default")
      (node (ref "U7") (pin "10") (pinfunction "NC_10") (pintype "unspecified+no_connect"))
    )
    (net (code "55") (name "unconnected-(U7-NC-Pad15)") (class "Default")
      (node (ref "U7") (pin "15") (pinfunction "NC_15") (pintype "unspecified+no_connect"))
    )
    (net (code "56") (name "unconnected-(U7-NC-Pad17)") (class "Default")
      (node (ref "U7") (pin "17") (pinfunction "NC_17") (pintype "unspecified+no_connect"))
    )
    (net (code "57") (name "unconnected-(U7-NC-Pad24)") (class "Default")
      (node (ref "U7") (pin "24") (pinfunction "NC_24") (pintype "unspecified+no_connect"))
    )
    (net (code "58") (name "unconnected-(U7-NC-Pad25)") (class "Default")
      (node (ref "U7") (pin "25") (pinfunction "NC_25") (pintype "unspecified+no_connect"))
    )
    (net (code "59") (name "unconnected-(U7-NC-Pad28)") (class "Default")
      (node (ref "U7") (pin "28") (pinfunction "NC_28") (pintype "unspecified+no_connect"))
    )
    (net (code "60") (name "unconnected-(U7-NC-Pad29)") (class "Default")
      (node (ref "U7") (pin "29") (pinfunction "NC_29") (pintype "unspecified+no_connect"))
    )
    (net (code "61") (name "unconnected-(U7-NC-Pad32)") (class "Default")
      (node (ref "U7") (pin "32") (pinfunction "NC_32") (pintype "unspecified+no_connect"))
    )
    (net (code "62") (name "unconnected-(U7-NC-Pad33)") (class "Default")
      (node (ref "U7") (pin "33") (pinfunction "NC_33") (pintype "unspecified+no_connect"))
    )
    (net (code "63") (name "unconnected-(U7-NC-Pad34)") (class "Default")
      (node (ref "U7") (pin "34") (pinfunction "NC_34") (pintype "unspecified+no_connect"))
    )
    (net (code "64") (name "unconnected-(U7-NC-Pad35)") (class "Default")
      (node (ref "U7") (pin "35") (pinfunction "NC_35") (pintype "unspecified+no_connect"))
    )
    (net (code "65") (name "unconnected-(USBC1-SBU1-PadA8)") (class "Default")
      (node (ref "USBC1") (pin "A8") (pinfunction "SBU1_A8") (pintype "unspecified+no_connect"))
    )
    (net (code "66") (name "unconnected-(USBC1-SBU2-PadB8)") (class "Default")
      (node (ref "USBC1") (pin "B8") (pinfunction "SBU2_B8") (pintype "unspecified+no_connect"))
    )
  )
)
